# MCU_SENSORS.net
KiCad netlist of a schematic drawn in Altium Designer
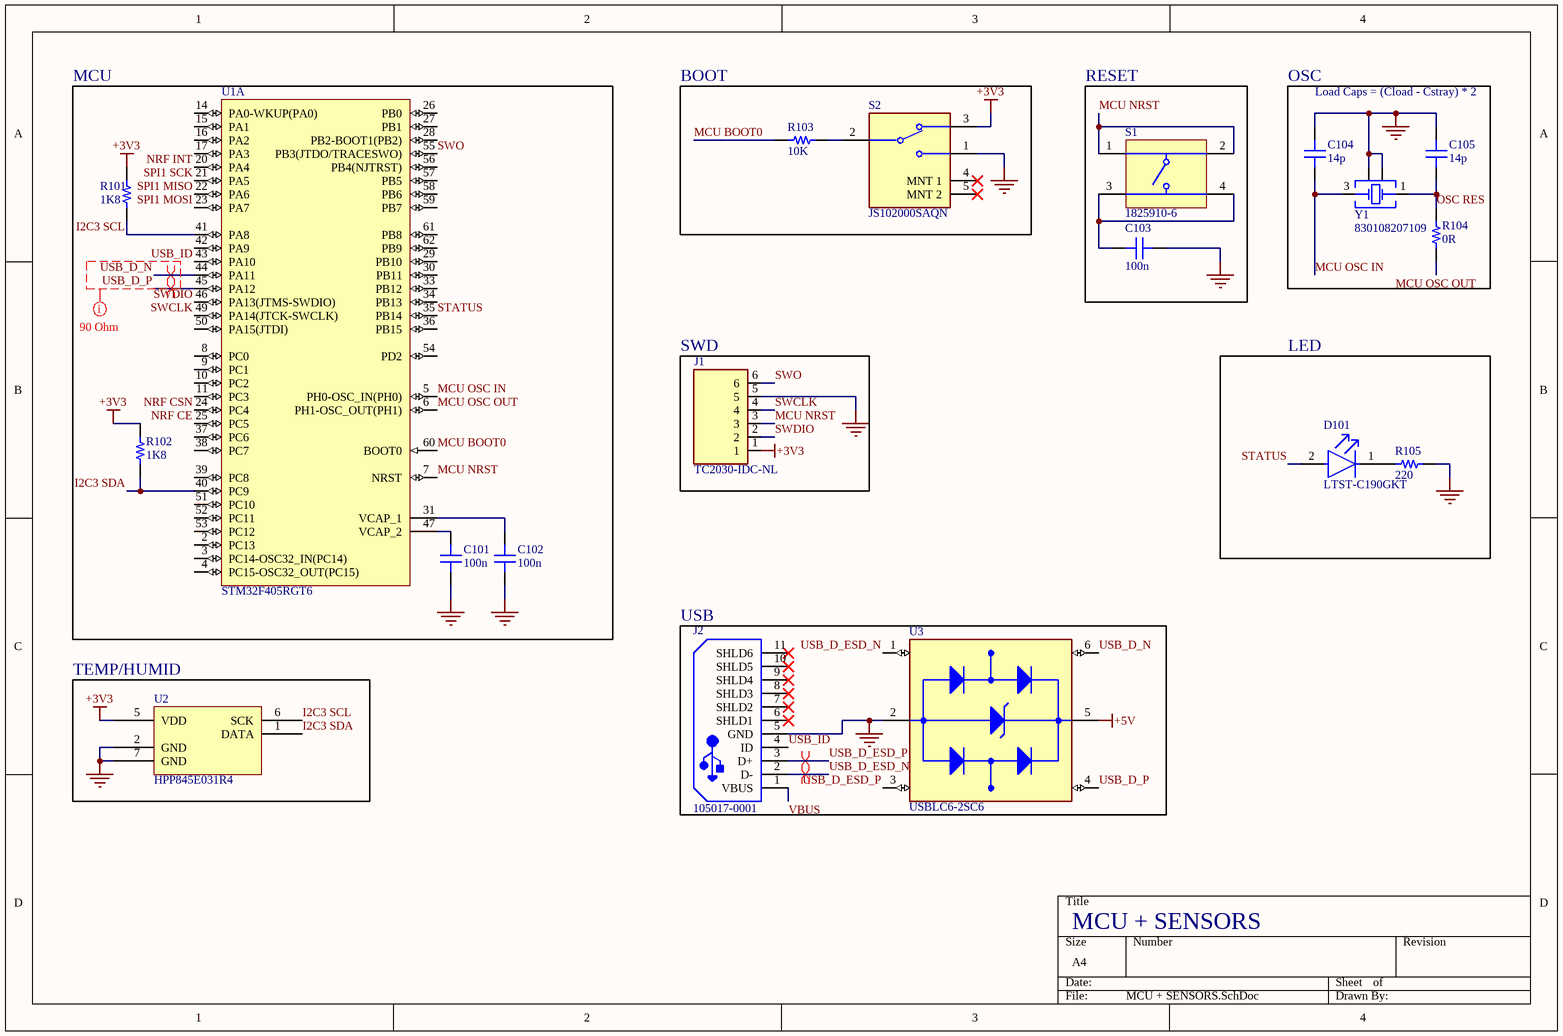
[diagram p0: MCU + SENSORS.SchDoc]

(export (version "E")
  (design (tool "Eeschema 10.0.6"))
  (components
    (comp (ref "C101")
      (value "100n")
      (footprint "CAP 0402_1005")
      (description "CAP CER 100NF 10V X7R 0402")
      (fields
        (field (name "PART NUMBER") "CL05B104KP5VPNC")
        (field (name "MANUFACTURER") "Samsung Electro-Mechanics")
      )
      (libsource (lib "Celestial Altium Library - altium_library") (part "Capacitor"))
    )
    (comp (ref "C102")
      (value "100n")
      (footprint "CAP 0402_1005")
      (description "CAP CER 100NF 10V X7R 0402")
      (fields
        (field (name "PART NUMBER") "CL05B104KP5VPNC")
        (field (name "MANUFACTURER") "Samsung Electro-Mechanics")
      )
      (libsource (lib "Celestial Altium Library - altium_library") (part "Capacitor"))
    )
    (comp (ref "C103")
      (value "100n")
      (footprint "CAP 0402_1005")
      (description "CAP CER 100NF 10V X7R 0402")
      (fields (field (name "PART NUMBER") "CL05B104KP5VPNC"))
      (libsource (lib "Celestial Altium Library - altium_library") (part "Capacitor"))
    )
    (comp (ref "C104")
      (value "14p")
      (footprint "CAP 0402_1005")
      (description "CAP CER 14PF 50V C0G/NP0 0402")
      (fields (field (name "PART NUMBER") "GJM1555C1H140GB01D"))
      (libsource (lib "Celestial Altium Library - altium_library") (part "Capacitor"))
    )
    (comp (ref "C105")
      (value "14p")
      (footprint "CAP 0402_1005")
      (description "CAP CER 14PF 50V C0G/NP0 0402")
      (fields (field (name "PART NUMBER") "GJM1555C1H140GB01D"))
      (libsource (lib "Celestial Altium Library - altium_library") (part "Capacitor"))
    )
    (comp (ref "D101")
      (value "LTST-C190GKT")
      (footprint "FP-LTST-C190GKT-MFG")
      (description "LED GREEN CLEAR CHIP SMD")
      (fields (field (name "VOLTAGE") "2V"))
      (libsource (lib "Altium Content Vault") (part "8706943c75ba83719d021d2fdc84c58"))
    )
    (comp (ref "J1")
      (value "TC2030-IDC-NL")
      (footprint "TAG_TC2030-IDC-NL")
      (description "CABLE ADAPTER 6 POS")
      (libsource (lib "TC2030-IDC-NL") (part "TC2030-IDC-NL"))
    )
    (comp (ref "J2")
      (value "105017-0001")
      (footprint "USB-MICRO-B_V")
      (fields (field (name "MANUFACTURER") "Molex"))
      (libsource (lib "Altium Content Vault") (part "USB-5-6SHLD"))
    )
    (comp (ref "R101")
      (value "1K8")
      (footprint "RES 0402_1005")
      (description "RES 10K OHM 0.1% 1/10W 0402")
      (fields (field (name "PART NUMBER") "RP73PF1E10KBTD"))
      (libsource (lib "Celestial Altium Library - altium_library") (part "Resistor"))
    )
    (comp (ref "R102")
      (value "1K8")
      (footprint "RES 0402_1005")
      (description "RES 10K OHM 0.1% 1/10W 0402")
      (fields (field (name "PART NUMBER") "RP73PF1E10KBTD"))
      (libsource (lib "Celestial Altium Library - altium_library") (part "Resistor"))
    )
    (comp (ref "R103")
      (value "10K")
      (footprint "RES 0402_1005")
      (description "RES 10K OHM 0.1% 1/10W 0402")
      (fields (field (name "PART NUMBER") "RP73PF1E10KBTD"))
      (libsource (lib "Celestial Altium Library - altium_library") (part "Resistor"))
    )
    (comp (ref "R104")
      (value "0R")
      (footprint "RES 0402_1005")
      (description "0402 JUMPER ON TAPE AND REEL")
      (fields (field (name "PART NUMBER") "5112"))
      (libsource (lib "Celestial Altium Library - altium_library") (part "Resistor"))
    )
    (comp (ref "R105")
      (value "220")
      (footprint "RES 0402_1005")
      (description "RES 10K OHM 0.1% 1/10W 0402")
      (fields (field (name "PART NUMBER") "RP73PF1E10KBTD"))
      (libsource (lib "Celestial Altium Library - altium_library") (part "Resistor"))
    )
    (comp (ref "S1")
      (value "1825910-6")
      (footprint "TECO-1825910-6_V")
      (description "Tact Switch, SPST-NO, 0.05 A, -35 to 85 degC, 4-Pin THD, RoHS, Bulk")
      (fields (field (name "MANUFACTURER") "TE Connectivity"))
      (libsource (lib "Altium Content Vault") (part "SW-SPST-4_A"))
    )
    (comp (ref "S2")
      (value "JS102000SAQN")
      (footprint "FP-JS102000SAQN-MFG")
      (description "SWITCH SLIDE SPDT 1MA 5V")
      (libsource (lib "Altium Content Vault") (part "6887e5fe807d9c5c2853bed39bc55bf"))
    )
    (comp (ref "U1")
      (value "STM32F405RGT6")
      (footprint "STM-LQFP64_M")
      (fields (field (name "MANUFACTURER") "STMicroelectronics"))
      (libsource (lib "Altium Content Vault") (part "MC-ARM-STM32F4X5-SQ64"))
    )
    (comp (ref "U2")
      (value "HPP845E031R4")
      (footprint "TE HPP845E031R4")
      (description "SENSOR HUMID/TEMP 3V I2C 2% SMD")
      (libsource (lib "Celestial Altium Library - altium_library") (part "TE HPP845E031R4"))
    )
    (comp (ref "U3")
      (value "USBLC6-2SC6")
      (footprint "SOT95P280X145-6N")
      (description "17V Clamp 5A (8/20Âµs) Ipp Tvs Diode Surface Mount SOT-23-6")
      (fields (field (name "MF") "STMicroelectronics"))
      (libsource (lib "USBLC6-2SC6") (part "USBLC6-2SC6"))
    )
    (comp (ref "Y1")
      (value "830108207109")
      (footprint "WE-XTAL_CFPX-180")
      (description "830108207109 WE-XTAL Quartz Crystal")
      (libsource (lib "Altium Content Vault") (part "WE-XTAL_CFPX-180"))
    )
  )
  (nets
    (net (code "1") (name "+3V3") (class "Default")
      (node (ref "J1") (pin "1") (pinfunction "1_1") (pintype "passive"))
      (node (ref "R101") (pin "2") (pinfunction "2_2") (pintype "passive"))
      (node (ref "R102") (pin "2") (pinfunction "2_2") (pintype "passive"))
      (node (ref "S2") (pin "3") (pinfunction "3_3") (pintype "passive"))
      (node (ref "U2") (pin "5") (pinfunction "VDD_5") (pintype "passive"))
    )
    (net (code "2") (name "+5V") (class "Default")
      (node (ref "U3") (pin "5") (pinfunction "VBUS_5") (pintype "power_in"))
    )
    (net (code "3") (name "/I2C3 SCL") (class "Default")
      (node (ref "R101") (pin "1") (pinfunction "1_1") (pintype "passive"))
      (node (ref "U1") (pin "41") (pinfunction "PA8_41") (pintype "bidirectional"))
      (node (ref "U2") (pin "6") (pinfunction "SCK_6") (pintype "passive"))
    )
    (net (code "4") (name "/I2C3 SDA") (class "Default")
      (node (ref "R102") (pin "1") (pinfunction "1_1") (pintype "passive"))
      (node (ref "U1") (pin "40") (pinfunction "PC9_40") (pintype "bidirectional"))
      (node (ref "U2") (pin "1") (pinfunction "DATA_1") (pintype "passive"))
    )
    (net (code "5") (name "/MCU BOOT0") (class "Default")
      (node (ref "R103") (pin "1") (pinfunction "1_1") (pintype "passive"))
      (node (ref "U1") (pin "60") (pinfunction "BOOT0_60") (pintype "input"))
    )
    (net (code "6") (name "/MCU NRST") (class "Default")
      (node (ref "J1") (pin "3") (pinfunction "3_3") (pintype "passive"))
      (node (ref "S1") (pin "1") (pinfunction "1_1") (pintype "passive"))
      (node (ref "S1") (pin "2") (pinfunction "2_2") (pintype "passive"))
      (node (ref "U1") (pin "7") (pinfunction "NRST_7") (pintype "bidirectional"))
    )
    (net (code "7") (name "/MCU OSC IN") (class "Default")
      (node (ref "C104") (pin "1") (pinfunction "1_1") (pintype "passive"))
      (node (ref "U1") (pin "5") (pinfunction "PH0-OSC_IN(PH0)_5") (pintype "bidirectional"))
      (node (ref "Y1") (pin "3") (pinfunction "Crystal_3") (pintype "passive"))
    )
    (net (code "8") (name "/MCU OSC OUT") (class "Default")
      (node (ref "R104") (pin "1") (pinfunction "1_1") (pintype "passive"))
      (node (ref "U1") (pin "6") (pinfunction "PH1-OSC_OUT(PH1)_6") (pintype "bidirectional"))
    )
    (net (code "9") (name "/NRF CE") (class "Default")
      (node (ref "U1") (pin "25") (pinfunction "PC5_25") (pintype "bidirectional"))
    )
    (net (code "10") (name "/NRF CSN") (class "Default")
      (node (ref "U1") (pin "24") (pinfunction "PC4_24") (pintype "bidirectional"))
    )
    (net (code "11") (name "/NRF INT") (class "Default")
      (node (ref "U1") (pin "20") (pinfunction "PA4_20") (pintype "bidirectional"))
    )
    (net (code "12") (name "/OSC RES") (class "Default")
      (node (ref "C105") (pin "1") (pinfunction "1_1") (pintype "passive"))
      (node (ref "R104") (pin "2") (pinfunction "2_2") (pintype "passive"))
      (node (ref "Y1") (pin "1") (pinfunction "Crystal_1") (pintype "passive"))
    )
    (net (code "13") (name "/SPI1 MISO") (class "Default")
      (node (ref "U1") (pin "22") (pinfunction "PA6_22") (pintype "bidirectional"))
    )
    (net (code "14") (name "/SPI1 MOSI") (class "Default")
      (node (ref "U1") (pin "23") (pinfunction "PA7_23") (pintype "bidirectional"))
    )
    (net (code "15") (name "/SPI1 SCK") (class "Default")
      (node (ref "U1") (pin "21") (pinfunction "PA5_21") (pintype "bidirectional"))
    )
    (net (code "16") (name "/STATUS") (class "Default")
      (node (ref "D101") (pin "2") (pinfunction "A_2") (pintype "passive"))
      (node (ref "U1") (pin "35") (pinfunction "PB14_35") (pintype "bidirectional"))
    )
    (net (code "17") (name "/SWCLK") (class "Default")
      (node (ref "J1") (pin "4") (pinfunction "4_4") (pintype "passive"))
      (node (ref "U1") (pin "49") (pinfunction "PA14(JTCK-SWCLK)_49") (pintype "bidirectional"))
    )
    (net (code "18") (name "/SWDIO") (class "Default")
      (node (ref "J1") (pin "2") (pinfunction "2_2") (pintype "passive"))
      (node (ref "U1") (pin "46") (pinfunction "PA13(JTMS-SWDIO)_46") (pintype "bidirectional"))
    )
    (net (code "19") (name "/SWO") (class "Default")
      (node (ref "J1") (pin "6") (pinfunction "6_6") (pintype "passive"))
      (node (ref "U1") (pin "55") (pinfunction "PB3(JTDO/TRACESWO)_55") (pintype "bidirectional"))
    )
    (net (code "20") (name "/USB_D_ESD_N") (class "Default")
      (node (ref "J2") (pin "2") (pinfunction "D-_2") (pintype "passive"))
      (node (ref "U3") (pin "1") (pinfunction "I/O1_IN_1") (pintype "bidirectional"))
    )
    (net (code "21") (name "/USB_D_ESD_P") (class "Default")
      (node (ref "J2") (pin "3") (pinfunction "D+_3") (pintype "passive"))
      (node (ref "U3") (pin "3") (pinfunction "I/O2_IN_3") (pintype "bidirectional"))
    )
    (net (code "22") (name "/USB_D_N") (class "Default")
      (node (ref "U1") (pin "44") (pinfunction "PA11_44") (pintype "bidirectional"))
      (node (ref "U3") (pin "6") (pinfunction "I/O1_OUT_6") (pintype "bidirectional"))
    )
    (net (code "23") (name "/USB_D_P") (class "Default")
      (node (ref "U1") (pin "45") (pinfunction "PA12_45") (pintype "bidirectional"))
      (node (ref "U3") (pin "4") (pinfunction "I/O2_OUT_4") (pintype "bidirectional"))
    )
    (net (code "24") (name "/USB_ID") (class "Default")
      (node (ref "J2") (pin "4") (pinfunction "ID_4") (pintype "passive"))
      (node (ref "U1") (pin "43") (pinfunction "PA10_43") (pintype "bidirectional"))
    )
    (net (code "25") (name "/VBUS") (class "Default")
      (node (ref "J2") (pin "1") (pinfunction "VBUS_1") (pintype "passive"))
    )
    (net (code "26") (name "GND") (class "Default")
      (node (ref "C101") (pin "1") (pinfunction "1_1") (pintype "passive"))
      (node (ref "C102") (pin "1") (pinfunction "1_1") (pintype "passive"))
      (node (ref "C103") (pin "1") (pinfunction "1_1") (pintype "passive"))
      (node (ref "C104") (pin "2") (pinfunction "2_2") (pintype "passive"))
      (node (ref "C105") (pin "2") (pinfunction "2_2") (pintype "passive"))
      (node (ref "J1") (pin "5") (pinfunction "5_5") (pintype "passive"))
      (node (ref "J2") (pin "5") (pinfunction "GND_5") (pintype "passive"))
      (node (ref "R105") (pin "2") (pinfunction "2_2") (pintype "passive"))
      (node (ref "S2") (pin "1") (pinfunction "1_1") (pintype "passive"))
      (node (ref "U2") (pin "2") (pinfunction "GND_2") (pintype "passive"))
      (node (ref "U2") (pin "7") (pinfunction "GND_7") (pintype "passive"))
      (node (ref "U3") (pin "2") (pinfunction "GND_2") (pintype "power_in"))
      (node (ref "Y1") (pin "2") (pinfunction "GND&Lid_2") (pintype "passive"))
      (node (ref "Y1") (pin "4") (pinfunction "GND&Lid_4") (pintype "passive"))
    )
    (net (code "27") (name "Net-(C103-Pad2)") (class "Default")
      (node (ref "C103") (pin "2") (pinfunction "2_2") (pintype "passive"))
      (node (ref "S1") (pin "3") (pinfunction "3_3") (pintype "passive"))
      (node (ref "S1") (pin "4") (pinfunction "4_4") (pintype "passive"))
    )
    (net (code "28") (name "Net-(D101-C)") (class "Default")
      (node (ref "D101") (pin "1") (pinfunction "C_1") (pintype "passive"))
      (node (ref "R105") (pin "1") (pinfunction "1_1") (pintype "passive"))
    )
    (net (code "29") (name "Net-(S2-C)") (class "Default")
      (node (ref "R103") (pin "2") (pinfunction "2_2") (pintype "passive"))
      (node (ref "S2") (pin "2") (pinfunction "C_2") (pintype "passive"))
    )
    (net (code "30") (name "Net-(U1A-VCAP_1)") (class "Default")
      (node (ref "C102") (pin "2") (pinfunction "2_2") (pintype "passive"))
      (node (ref "U1") (pin "31") (pinfunction "VCAP_1_31") (pintype "power_in"))
    )
    (net (code "31") (name "Net-(U1A-VCAP_2)") (class "Default")
      (node (ref "C101") (pin "2") (pinfunction "2_2") (pintype "passive"))
      (node (ref "U1") (pin "47") (pinfunction "VCAP_2_47") (pintype "power_in"))
    )
    (net (code "32") (name "unconnected-(J2-SHLD1-Pad6)") (class "Default")
      (node (ref "J2") (pin "6") (pinfunction "SHLD1_6") (pintype "passive+no_connect"))
    )
    (net (code "33") (name "unconnected-(J2-SHLD2-Pad7)") (class "Default")
      (node (ref "J2") (pin "7") (pinfunction "SHLD2_7") (pintype "passive+no_connect"))
    )
    (net (code "34") (name "unconnected-(J2-SHLD3-Pad8)") (class "Default")
      (node (ref "J2") (pin "8") (pinfunction "SHLD3_8") (pintype "passive+no_connect"))
    )
    (net (code "35") (name "unconnected-(J2-SHLD4-Pad9)") (class "Default")
      (node (ref "J2") (pin "9") (pinfunction "SHLD4_9") (pintype "passive+no_connect"))
    )
    (net (code "36") (name "unconnected-(J2-SHLD5-Pad10)") (class "Default")
      (node (ref "J2") (pin "10") (pinfunction "SHLD5_10") (pintype "passive+no_connect"))
    )
    (net (code "37") (name "unconnected-(J2-SHLD6-Pad11)") (class "Default")
      (node (ref "J2") (pin "11") (pinfunction "SHLD6_11") (pintype "passive+no_connect"))
    )
    (net (code "38") (name "unconnected-(S2-MNT_1-Pad4)") (class "Default")
      (node (ref "S2") (pin "4") (pinfunction "MNT_1_4") (pintype "passive+no_connect"))
    )
    (net (code "39") (name "unconnected-(S2-MNT_2-Pad5)") (class "Default")
      (node (ref "S2") (pin "5") (pinfunction "MNT_2_5") (pintype "passive+no_connect"))
    )
    (net (code "40") (name "unconnected-(U1A-PA0-WKUP(PA0)-Pad14)") (class "Default")
      (node (ref "U1") (pin "14") (pinfunction "PA0-WKUP(PA0)_14") (pintype "bidirectional"))
    )
    (net (code "41") (name "unconnected-(U1A-PA1-Pad15)") (class "Default")
      (node (ref "U1") (pin "15") (pinfunction "PA1_15") (pintype "bidirectional"))
    )
    (net (code "42") (name "unconnected-(U1A-PA2-Pad16)") (class "Default")
      (node (ref "U1") (pin "16") (pinfunction "PA2_16") (pintype "bidirectional"))
    )
    (net (code "43") (name "unconnected-(U1A-PA3-Pad17)") (class "Default")
      (node (ref "U1") (pin "17") (pinfunction "PA3_17") (pintype "bidirectional"))
    )
    (net (code "44") (name "unconnected-(U1A-PA9-Pad42)") (class "Default")
      (node (ref "U1") (pin "42") (pinfunction "PA9_42") (pintype "bidirectional"))
    )
    (net (code "45") (name "unconnected-(U1A-PA15(JTDI)-Pad50)") (class "Default")
      (node (ref "U1") (pin "50") (pinfunction "PA15(JTDI)_50") (pintype "bidirectional"))
    )
    (net (code "46") (name "unconnected-(U1A-PB0-Pad26)") (class "Default")
      (node (ref "U1") (pin "26") (pinfunction "PB0_26") (pintype "bidirectional"))
    )
    (net (code "47") (name "unconnected-(U1A-PB1-Pad27)") (class "Default")
      (node (ref "U1") (pin "27") (pinfunction "PB1_27") (pintype "bidirectional"))
    )
    (net (code "48") (name "unconnected-(U1A-PB2-BOOT1(PB2)-Pad28)") (class "Default")
      (node (ref "U1") (pin "28") (pinfunction "PB2-BOOT1(PB2)_28") (pintype "bidirectional"))
    )
    (net (code "49") (name "unconnected-(U1A-PB4(NJTRST)-Pad56)") (class "Default")
      (node (ref "U1") (pin "56") (pinfunction "PB4(NJTRST)_56") (pintype "bidirectional"))
    )
    (net (code "50") (name "unconnected-(U1A-PB5-Pad57)") (class "Default")
      (node (ref "U1") (pin "57") (pinfunction "PB5_57") (pintype "bidirectional"))
    )
    (net (code "51") (name "unconnected-(U1A-PB6-Pad58)") (class "Default")
      (node (ref "U1") (pin "58") (pinfunction "PB6_58") (pintype "bidirectional"))
    )
    (net (code "52") (name "unconnected-(U1A-PB7-Pad59)") (class "Default")
      (node (ref "U1") (pin "59") (pinfunction "PB7_59") (pintype "bidirectional"))
    )
    (net (code "53") (name "unconnected-(U1A-PB8-Pad61)") (class "Default")
      (node (ref "U1") (pin "61") (pinfunction "PB8_61") (pintype "bidirectional"))
    )
    (net (code "54") (name "unconnected-(U1A-PB9-Pad62)") (class "Default")
      (node (ref "U1") (pin "62") (pinfunction "PB9_62") (pintype "bidirectional"))
    )
    (net (code "55") (name "unconnected-(U1A-PB10-Pad29)") (class "Default")
      (node (ref "U1") (pin "29") (pinfunction "PB10_29") (pintype "bidirectional"))
    )
    (net (code "56") (name "unconnected-(U1A-PB11-Pad30)") (class "Default")
      (node (ref "U1") (pin "30") (pinfunction "PB11_30") (pintype "bidirectional"))
    )
    (net (code "57") (name "unconnected-(U1A-PB12-Pad33)") (class "Default")
      (node (ref "U1") (pin "33") (pinfunction "PB12_33") (pintype "bidirectional"))
    )
    (net (code "58") (name "unconnected-(U1A-PB13-Pad34)") (class "Default")
      (node (ref "U1") (pin "34") (pinfunction "PB13_34") (pintype "bidirectional"))
    )
    (net (code "59") (name "unconnected-(U1A-PB15-Pad36)") (class "Default")
      (node (ref "U1") (pin "36") (pinfunction "PB15_36") (pintype "bidirectional"))
    )
    (net (code "60") (name "unconnected-(U1A-PC0-Pad8)") (class "Default")
      (node (ref "U1") (pin "8") (pinfunction "PC0_8") (pintype "bidirectional"))
    )
    (net (code "61") (name "unconnected-(U1A-PC1-Pad9)") (class "Default")
      (node (ref "U1") (pin "9") (pinfunction "PC1_9") (pintype "bidirectional"))
    )
    (net (code "62") (name "unconnected-(U1A-PC2-Pad10)") (class "Default")
      (node (ref "U1") (pin "10") (pinfunction "PC2_10") (pintype "bidirectional"))
    )
    (net (code "63") (name "unconnected-(U1A-PC3-Pad11)") (class "Default")
      (node (ref "U1") (pin "11") (pinfunction "PC3_11") (pintype "bidirectional"))
    )
    (net (code "64") (name "unconnected-(U1A-PC6-Pad37)") (class "Default")
      (node (ref "U1") (pin "37") (pinfunction "PC6_37") (pintype "bidirectional"))
    )
    (net (code "65") (name "unconnected-(U1A-PC7-Pad38)") (class "Default")
      (node (ref "U1") (pin "38") (pinfunction "PC7_38") (pintype "bidirectional"))
    )
    (net (code "66") (name "unconnected-(U1A-PC8-Pad39)") (class "Default")
      (node (ref "U1") (pin "39") (pinfunction "PC8_39") (pintype "bidirectional"))
    )
    (net (code "67") (name "unconnected-(U1A-PC10-Pad51)") (class "Default")
      (node (ref "U1") (pin "51") (pinfunction "PC10_51") (pintype "bidirectional"))
    )
    (net (code "68") (name "unconnected-(U1A-PC11-Pad52)") (class "Default")
      (node (ref "U1") (pin "52") (pinfunction "PC11_52") (pintype "bidirectional"))
    )
    (net (code "69") (name "unconnected-(U1A-PC12-Pad53)") (class "Default")
      (node (ref "U1") (pin "53") (pinfunction "PC12_53") (pintype "bidirectional"))
    )
    (net (code "70") (name "unconnected-(U1A-PC13-Pad2)") (class "Default")
      (node (ref "U1") (pin "2") (pinfunction "PC13_2") (pintype "bidirectional"))
    )
    (net (code "71") (name "unconnected-(U1A-PC14-OSC32_IN(PC14)-Pad3)") (class "Default")
      (node (ref "U1") (pin "3") (pinfunction "PC14-OSC32_IN(PC14)_3") (pintype "bidirectional"))
    )
    (net (code "72") (name "unconnected-(U1A-PC15-OSC32_OUT(PC15)-Pad4)") (class "Default")
      (node (ref "U1") (pin "4") (pinfunction "PC15-OSC32_OUT(PC15)_4") (pintype "bidirectional"))
    )
    (net (code "73") (name "unconnected-(U1A-PD2-Pad54)") (class "Default")
      (node (ref "U1") (pin "54") (pinfunction "PD2_54") (pintype "bidirectional"))
    )
  )
)
